# 100W_Inverter_V1_Sch.net
KiCad netlist of a schematic drawn in Altium Designer
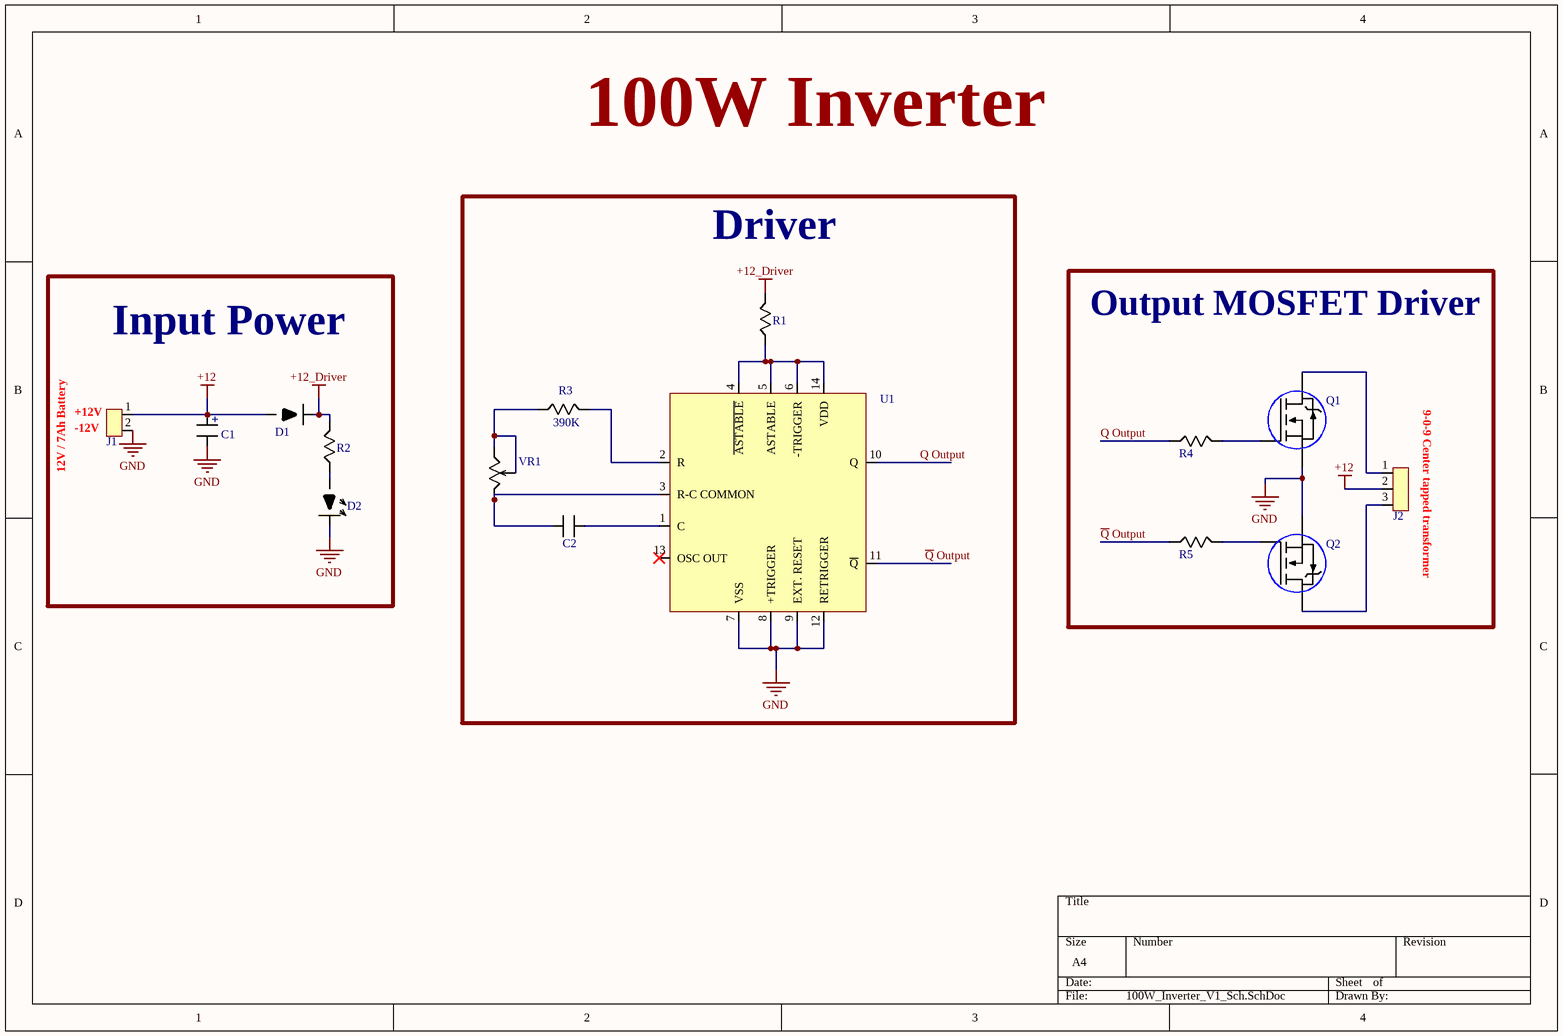
[diagram p0: 100W_Inverter_V1_Sch.SchDoc]

(export (version "E")
  (design (tool "Eeschema 10.0.6"))
  (components
    (comp (ref "C1")
      (value "C_2200uF_Ely_35V_TH")
      (footprint "Ecap_8mmPitch_16d")
      (fields (field (name "TOLERANCE") "20%"))
      (libsource (lib "Sch_common") (part "C_2200uF_Ely_35V_TH"))
    )
    (comp (ref "C2")
      (value "C_0.01uF_Cer_50V_TH")
      (footprint "0.01uF_Cer_TH")
      (description "Capacitor Ceramic 0.01uF 50V C0G 5% 5mm T/R")
      (fields (field (name "TOLERANCE") "5%"))
      (libsource (lib "Sch_common") (part "C_0.01uF_Cer_50V_TH"))
    )
    (comp (ref "D1")
      (value "1N4007")
      (footprint "Diode")
      (description "Diode Switching 1KV 1A 2-Pin DO-41 T/R")
      (libsource (lib "Sch_common") (part "1N4007"))
    )
    (comp (ref "D2")
      (value "LED_3mm_Red_TH")
      (footprint "LED_3MM_Red")
      (libsource (lib "Sch_common") (part "LED_3mm_Red_TH"))
    )
    (comp (ref "J1")
      (value "TB_2P_5mmP")
      (footprint "TB_5mmP_2Pin")
      (description "TERM BLOCK PLUG 2POS 90DEG 5MM")
      (fields (field (name "VOLTAGE") "300V"))
      (libsource (lib "Sch_common") (part "TB_2P_5mmP"))
    )
    (comp (ref "J2")
      (value "TB_3P_5mmP")
      (footprint "TB_5mmP_3Pin")
      (description "Res Thick Film 0603 100K Ohm 1% 0.1W(1/10W) ±100ppm/C Pad SMD Automotive T/R")
      (fields (field (name "TOLERANCE") "1%"))
      (libsource (lib "Sch_common") (part "TB_3P_5mmP"))
    )
    (comp (ref "Q1")
      (value "IRF540")
      (footprint "TO220")
      (description "Mosfet, Power; N-ch; Vdss 100V; Rds(on) 21MILLIOHMS; Id 36A; TO-262; Pd 92W; Vgs +/-20")
      (libsource (lib "Sch_common") (part "IRF540"))
    )
    (comp (ref "Q2")
      (value "IRF540")
      (footprint "TO220")
      (description "Mosfet, Power; N-ch; Vdss 100V; Rds(on) 21MILLIOHMS; Id 36A; TO-262; Pd 92W; Vgs +/-20")
      (libsource (lib "Sch_common") (part "IRF540"))
    )
    (comp (ref "R1")
      (value "R_330_0.25W_TH")
      (footprint "Axial 0.3")
      (description "TE Connectivity CFR16 Series Axial Carbon Film Resistor 330 5% 0.25W -1200  0ppm/C")
      (fields (field (name "TOLERANCE") "5%"))
      (libsource (lib "Sch_common") (part "R_330_0.25W_TH"))
    )
    (comp (ref "R2")
      (value "R_1K_0.25W_TH")
      (footprint "Axial 0.3")
      (description "TE Connectivity CFR16 Series Axial Carbon Film Resistor 1k 5% 0.25W -1200  0ppm/C")
      (fields (field (name "TOLERANCE") "5%"))
      (libsource (lib "Sch_common") (part "R_1K_0.25W_TH"))
    )
    (comp (ref "R3")
      (value "390K")
      (footprint "Axial 0.3")
      (description "RES 390K OHM 1/4W 5% AXIAL")
      (fields (field (name "TOLERANCE") "5%"))
      (libsource (lib "Sch_common") (part "R_390K_0.25W_TH"))
    )
    (comp (ref "R4")
      (value "R_220_0.25W_TH")
      (footprint "Axial 0.3")
      (description "RES 220 OHM 1/4W 5% AXIAL")
      (fields (field (name "TOLERANCE") "5%"))
      (libsource (lib "Sch_common") (part "R_220_0.25W_TH"))
    )
    (comp (ref "R5")
      (value "R_220_0.25W_TH")
      (footprint "Axial 0.3")
      (description "RES 220 OHM 1/4W 5% AXIAL")
      (fields (field (name "TOLERANCE") "5%"))
      (libsource (lib "Sch_common") (part "R_220_0.25W_TH"))
    )
    (comp (ref "U1")
      (value "CD4047BE")
      (footprint "DIP14_8mmspace_2.54mmP")
      (libsource (lib "Sch_common") (part "CD4047BE"))
    )
    (comp (ref "VR1")
      (value "VR_1K_trim_20T")
      (footprint "3290H")
      (description "TRIMMER 1K OHM 1W PC PIN")
      (fields (field (name "TOLERANCE") "5%"))
      (libsource (lib "Sch_common") (part "VR_1K_trim_20T"))
    )
  )
  (nets
    (net (code "1") (name "+12") (class "Default")
      (node (ref "C1") (pin "1") (pinfunction "1_1") (pintype "passive"))
      (node (ref "D1") (pin "1") (pinfunction "1_1") (pintype "passive"))
      (node (ref "J1") (pin "1") (pinfunction "1_1") (pintype "passive"))
      (node (ref "J2") (pin "2") (pinfunction "2_2") (pintype "passive"))
    )
    (net (code "2") (name "+12_Driver") (class "Default")
      (node (ref "D1") (pin "2") (pinfunction "2_2") (pintype "passive"))
      (node (ref "R1") (pin "2") (pinfunction "2_2") (pintype "passive"))
      (node (ref "R2") (pin "2") (pinfunction "2_2") (pintype "passive"))
    )
    (net (code "3") (name "/Q Output") (class "Default")
      (node (ref "R4") (pin "1") (pinfunction "1_1") (pintype "passive"))
      (node (ref "U1") (pin "10") (pinfunction "Q_10") (pintype "passive"))
    )
    (net (code "4") (name "/~{Q} Output") (class "Default")
      (node (ref "R5") (pin "1") (pinfunction "1_1") (pintype "passive"))
      (node (ref "U1") (pin "11") (pinfunction "~{Q}_11") (pintype "passive"))
    )
    (net (code "5") (name "GND") (class "Default")
      (node (ref "C1") (pin "2") (pinfunction "2_2") (pintype "passive"))
      (node (ref "D2") (pin "2") (pinfunction "2_2") (pintype "passive"))
      (node (ref "J1") (pin "2") (pinfunction "2_2") (pintype "passive"))
      (node (ref "Q1") (pin "3") (pinfunction "3_3") (pintype "passive"))
      (node (ref "Q2") (pin "3") (pinfunction "3_3") (pintype "passive"))
      (node (ref "U1") (pin "12") (pinfunction "RETRIGGER_12") (pintype "passive"))
      (node (ref "U1") (pin "7") (pinfunction "VSS_7") (pintype "passive"))
      (node (ref "U1") (pin "8") (pinfunction "+TRIGGER_8") (pintype "passive"))
      (node (ref "U1") (pin "9") (pinfunction "EXT._RESET_9") (pintype "passive"))
    )
    (net (code "6") (name "Net-(D2-Pad1)") (class "Default")
      (node (ref "D2") (pin "1") (pinfunction "1_1") (pintype "passive"))
      (node (ref "R2") (pin "1") (pinfunction "1_1") (pintype "passive"))
    )
    (net (code "7") (name "Net-(J2-Pad1)") (class "Default")
      (node (ref "J2") (pin "1") (pinfunction "1_1") (pintype "passive"))
      (node (ref "Q1") (pin "2") (pinfunction "2_2") (pintype "passive"))
    )
    (net (code "8") (name "Net-(J2-Pad3)") (class "Default")
      (node (ref "J2") (pin "3") (pinfunction "3_3") (pintype "passive"))
      (node (ref "Q2") (pin "2") (pinfunction "2_2") (pintype "passive"))
    )
    (net (code "9") (name "Net-(Q1-Pad1)") (class "Default")
      (node (ref "Q1") (pin "1") (pinfunction "1_1") (pintype "passive"))
      (node (ref "R4") (pin "2") (pinfunction "2_2") (pintype "passive"))
    )
    (net (code "10") (name "Net-(Q2-Pad1)") (class "Default")
      (node (ref "Q2") (pin "1") (pinfunction "1_1") (pintype "passive"))
      (node (ref "R5") (pin "2") (pinfunction "2_2") (pintype "passive"))
    )
    (net (code "11") (name "Net-(R3-Pad1)") (class "Default")
      (node (ref "R3") (pin "1") (pinfunction "1_1") (pintype "passive"))
      (node (ref "VR1") (pin "1") (pinfunction "1_1") (pintype "passive"))
      (node (ref "VR1") (pin "2") (pinfunction "2_2") (pintype "passive"))
    )
    (net (code "12") (name "Net-(U1--TRIGGER)") (class "Default")
      (node (ref "R1") (pin "1") (pinfunction "1_1") (pintype "passive"))
      (node (ref "U1") (pin "14") (pinfunction "VDD_14") (pintype "passive"))
      (node (ref "U1") (pin "4") (pinfunction "~{ASTABLE}_4") (pintype "passive"))
      (node (ref "U1") (pin "5") (pinfunction "ASTABLE_5") (pintype "passive"))
      (node (ref "U1") (pin "6") (pinfunction "-TRIGGER_6") (pintype "passive"))
    )
    (net (code "13") (name "Net-(U1-C)") (class "Default")
      (node (ref "C2") (pin "2") (pinfunction "2_2") (pintype "passive"))
      (node (ref "U1") (pin "1") (pinfunction "C_1") (pintype "passive"))
    )
    (net (code "14") (name "Net-(U1-R)") (class "Default")
      (node (ref "R3") (pin "2") (pinfunction "2_2") (pintype "passive"))
      (node (ref "U1") (pin "2") (pinfunction "R_2") (pintype "passive"))
    )
    (net (code "15") (name "Net-(U1-R-C_COMMON)") (class "Default")
      (node (ref "C2") (pin "1") (pinfunction "1_1") (pintype "passive"))
      (node (ref "U1") (pin "3") (pinfunction "R-C_COMMON_3") (pintype "passive"))
      (node (ref "VR1") (pin "3") (pinfunction "3_3") (pintype "passive"))
    )
    (net (code "16") (name "unconnected-(U1-OSC_OUT-Pad13)") (class "Default")
      (node (ref "U1") (pin "13") (pinfunction "OSC_OUT_13") (pintype "passive+no_connect"))
    )
  )
)
